# AUDIO_AMP_MAX9812L.net
KiCad netlist of a schematic drawn in Altium Designer
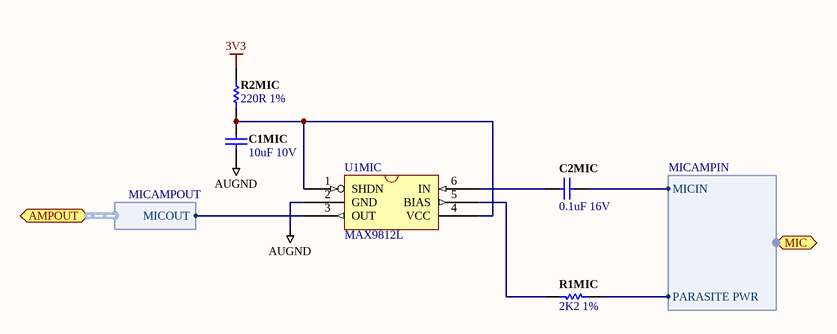
[diagram p0: AUDIO_AMP_MAX9812L.SchDoc]

(export (version "E")
  (design (tool "Eeschema 10.0.6"))
  (components
    (comp (ref "C1MIC")
      (value "10uF 10V")
      (footprint "CAPC2012-STAR")
      (description "Capacitor, Ceramic, 10uF 10% 10V 0805 (2012) X5R")
      (fields (field (name "TOLERANCE") "10 %"))
      (libsource (lib "altium-import") (part "root_2_mirrored_CAP-NP_"))
    )
    (comp (ref "C2MIC")
      (value "0.1uF 16V")
      (footprint "CAPC1005-STAR")
      (description "Capacitor, Ceramic, 0.1uF 10% 16V 0402 (1005) X7R")
      (fields (field (name "TOLERANCE") "10 %"))
      (libsource (lib "altium-import") (part "root_1_mirrored_CAP-NP_"))
    )
    (comp (ref "R1MIC")
      (value "2K2 1%")
      (footprint "RESC1005-STAR")
      (description "Resistor, 2K2 1% 0402 (1005)")
      (fields (field (name "TOLERANCE") "1 %"))
      (libsource (lib "altium-import") (part "root_3_mirrored_RES_"))
    )
    (comp (ref "R2MIC")
      (value "220R 1%")
      (footprint "RESC1005-STAR")
      (description "Resistor, 220R 1% 0402 (1005)")
      (fields (field (name "TOLERANCE") "1 %"))
      (libsource (lib "altium-import") (part "root_2_RES_"))
    )
    (comp (ref "U1MIC")
      (value "MAX9812L")
      (footprint "SC70_6L")
      (description "MAX9812L, Microphone Pre-Amplifier, single, 20dB gain, Shutdown")
      (libsource (lib "AltiumDesignLibrary") (part "MAX9812"))
    )
  )
  (nets
    (net (code "3") (name "/MICIN") (class "Default")
      (node (ref "C2MIC") (pin "1") (pinfunction "1_1") (pintype "passive"))
    )
    (net (code "4") (name "/MICOUT") (class "Default")
      (node (ref "U1MIC") (pin "3") (pinfunction "OUT_3") (pintype "output"))
    )
    (net (code "5") (name "/PARASITE PWR") (class "Default")
      (node (ref "R1MIC") (pin "2") (pinfunction "2_2") (pintype "passive"))
    )
    (net (code "8") (name "3V3") (class "Default")
      (node (ref "R2MIC") (pin "2") (pinfunction "2_2") (pintype "passive"))
    )
    (net (code "9") (name "AUGND") (class "Default")
      (node (ref "C1MIC") (pin "1") (pinfunction "1_1") (pintype "passive"))
      (node (ref "U1MIC") (pin "2") (pinfunction "GND_2") (pintype "power_in"))
    )
    (net (code "10") (name "Net-(U1MIC-BIAS)") (class "Default")
      (node (ref "R1MIC") (pin "1") (pinfunction "1_1") (pintype "passive"))
      (node (ref "U1MIC") (pin "5") (pinfunction "BIAS_5") (pintype "output"))
    )
    (net (code "11") (name "Net-(U1MIC-IN)") (class "Default")
      (node (ref "C2MIC") (pin "2") (pinfunction "2_2") (pintype "passive"))
      (node (ref "U1MIC") (pin "6") (pinfunction "IN_6") (pintype "input"))
    )
    (net (code "12") (name "Net-(U1MIC-SHDN)") (class "Default")
      (node (ref "C1MIC") (pin "2") (pinfunction "2_2") (pintype "passive"))
      (node (ref "R2MIC") (pin "1") (pinfunction "1_1") (pintype "passive"))
      (node (ref "U1MIC") (pin "1") (pinfunction "SHDN_1") (pintype "input"))
      (node (ref "U1MIC") (pin "4") (pinfunction "VCC_4") (pintype "power_in"))
    )
  )
)
